# external.net
KiCad netlist of a schematic drawn in EAGLE
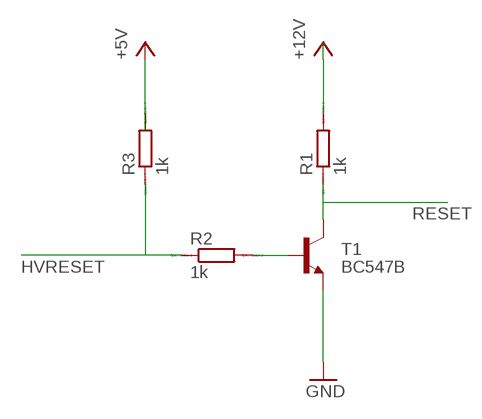
[diagram p0: schematic, sheet 1]

(export (version "E")
  (design (tool "Eeschema 10.0.6"))
  (components
    (comp (ref "R1")
      (value "1k")
      (footprint "eagle-import:R0805")
      (libsource (lib "eagle-import") (part "R"))
    )
    (comp (ref "R2")
      (value "1k")
      (footprint "eagle-import:R0805")
      (libsource (lib "eagle-import") (part "R"))
    )
    (comp (ref "R3")
      (value "1k")
      (footprint "eagle-import:R0805")
      (libsource (lib "eagle-import") (part "R"))
    )
    (comp (ref "T1")
      (value "BC547B")
      (footprint "eagle-import:TO92")
      (libsource (lib "eagle-import") (part "BC547"))
    )
  )
  (nets
    (net (code "1") (name "+12V") (class "Default")
      (node (ref "R1") (pin "2") (pinfunction "2_2") (pintype "passive"))
      (node (ref "R3") (pin "2") (pinfunction "2_2") (pintype "passive"))
    )
    (net (code "2") (name "/HVRESET") (class "Default")
      (node (ref "R2") (pin "1") (pinfunction "1_1") (pintype "passive"))
    )
    (net (code "4") (name "GND") (class "Default")
      (node (ref "T1") (pin "1") (pinfunction "E_1") (pintype "passive"))
    )
    (net (code "5") (name "Net-(T1-B)") (class "Default")
      (node (ref "R2") (pin "2") (pinfunction "2_2") (pintype "passive"))
      (node (ref "T1") (pin "2") (pinfunction "B_2") (pintype "passive"))
    )
    (net (code "6") (name "Net-(T1-C)") (class "Default")
      (node (ref "R1") (pin "1") (pinfunction "1_1") (pintype "passive"))
      (node (ref "T1") (pin "3") (pinfunction "C_3") (pintype "passive"))
    )
    (net (code "7") (name "unconnected-(R3-Pad1)") (class "Default")
      (node (ref "R3") (pin "1") (pinfunction "1_1") (pintype "passive"))
    )
  )
)
